# gimbal_controller.net
KiCad netlist of a schematic drawn in EAGLE
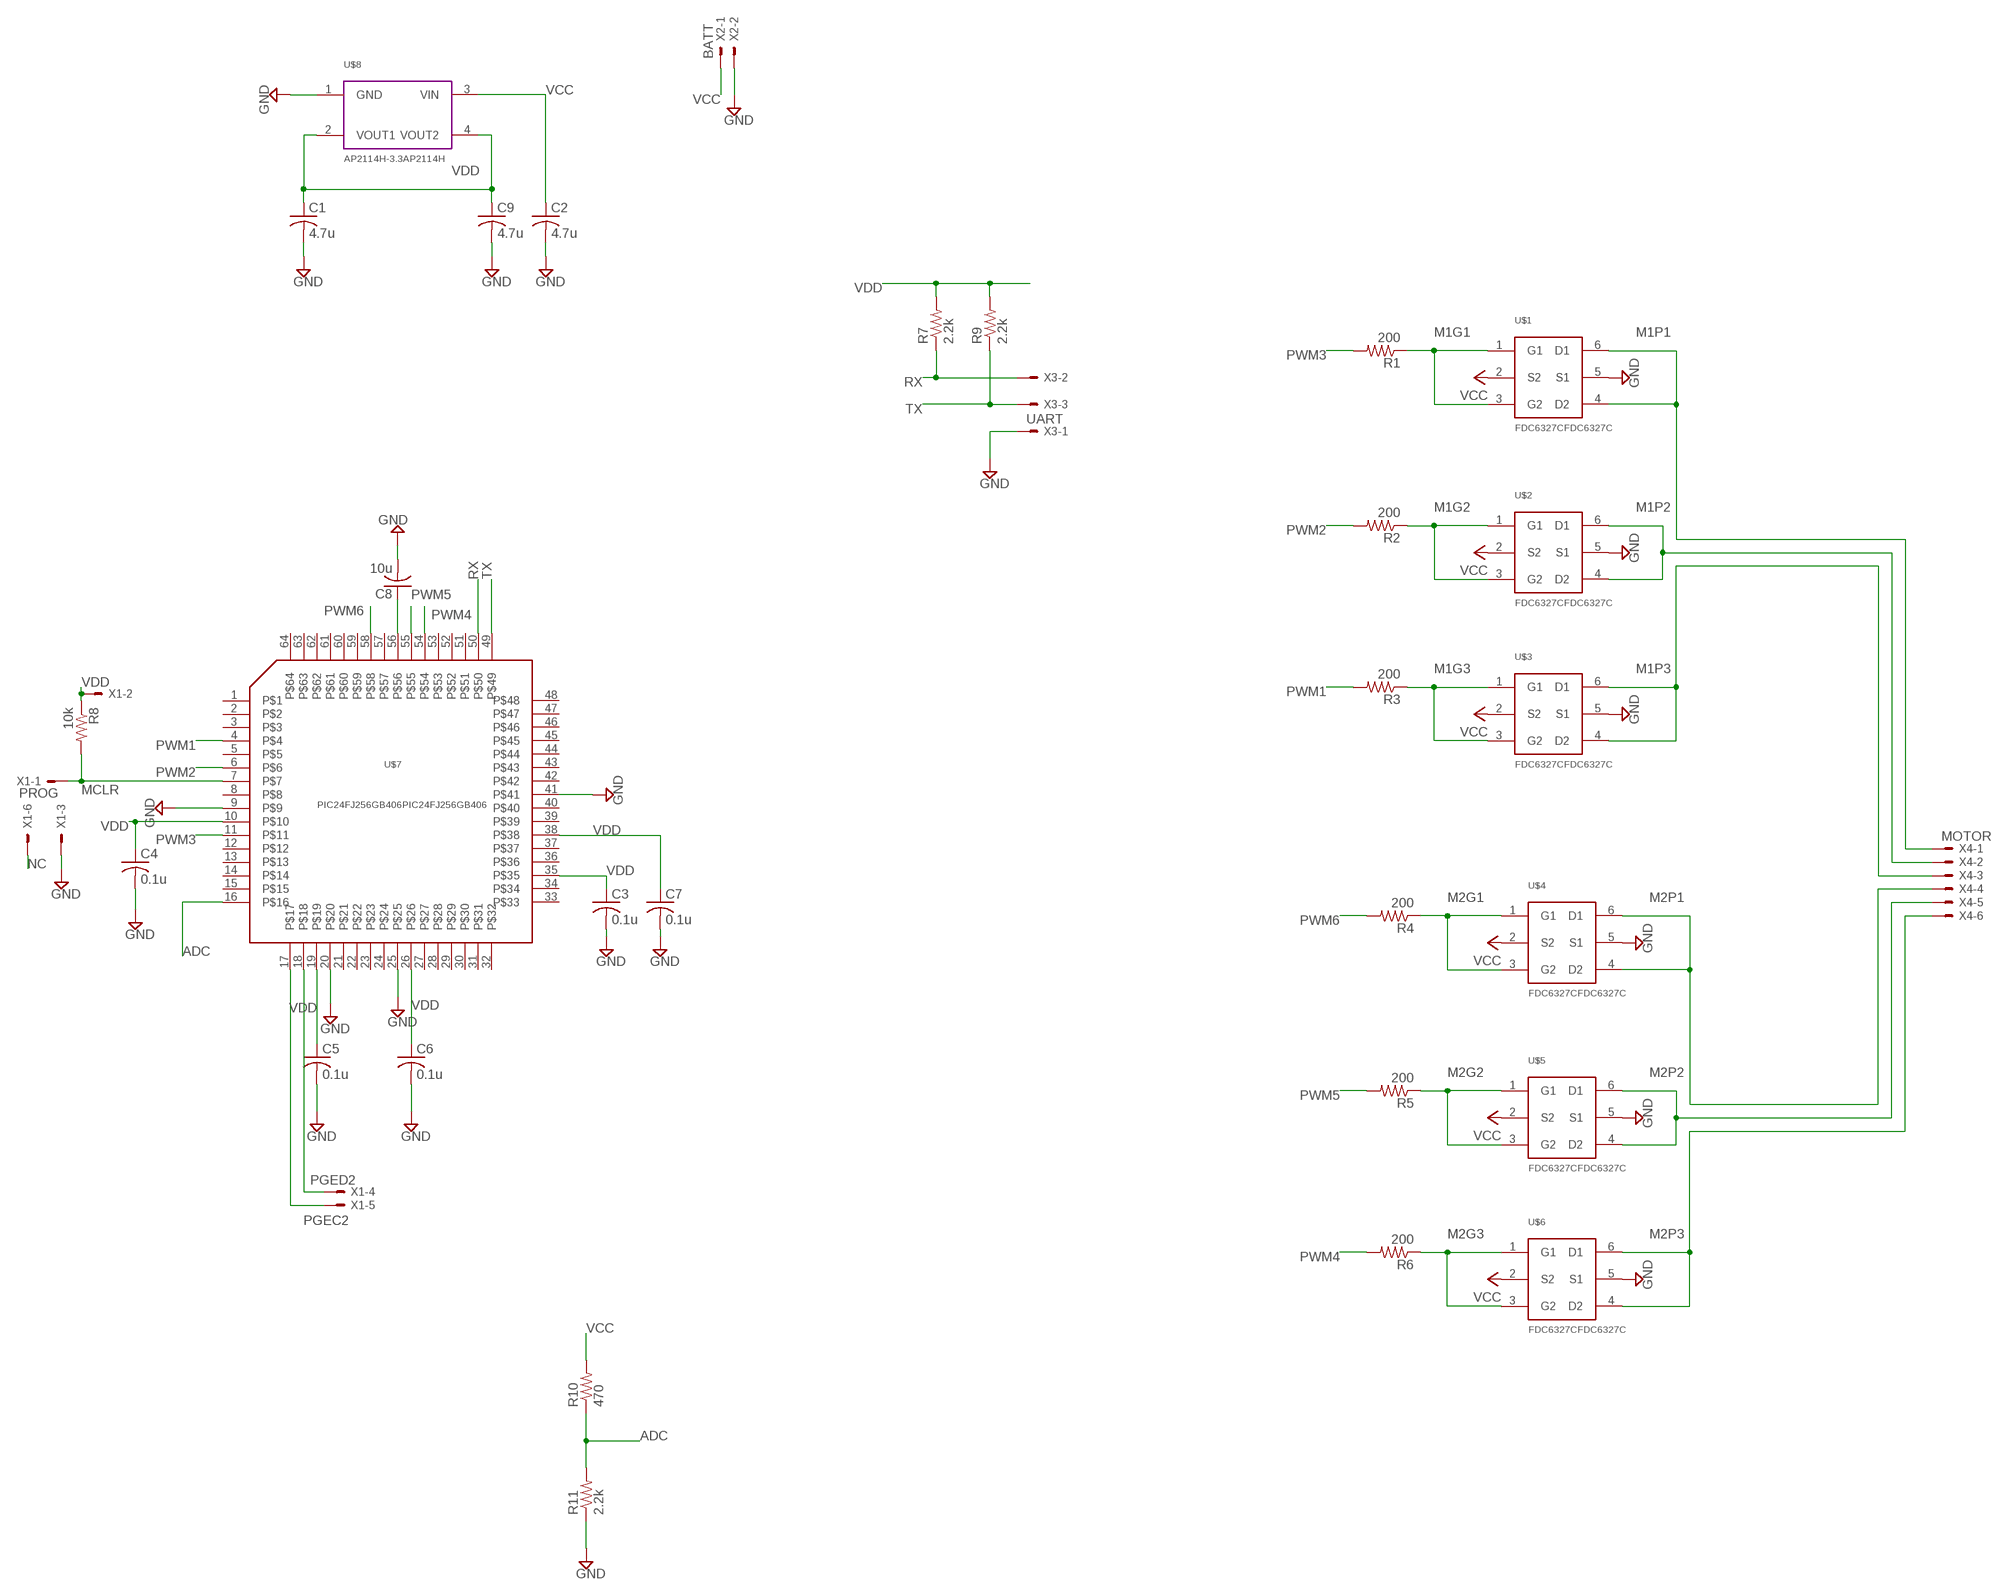
[diagram p0: schematic, sheet 1]

(export (version "E")
  (design (tool "Eeschema 10.0.6"))
  (components
    (comp (ref "C1")
      (value "4.7u")
      (footprint "eagle-import:C0805")
      (libsource (lib "eagle-import") (part "C-USC0805"))
    )
    (comp (ref "C2")
      (value "4.7u")
      (footprint "eagle-import:C0805")
      (libsource (lib "eagle-import") (part "C-USC0805"))
    )
    (comp (ref "C3")
      (value "0.1u")
      (footprint "eagle-import:C0805")
      (libsource (lib "eagle-import") (part "C-USC0805"))
    )
    (comp (ref "C4")
      (value "0.1u")
      (footprint "eagle-import:C0805")
      (libsource (lib "eagle-import") (part "C-USC0805"))
    )
    (comp (ref "C5")
      (value "0.1u")
      (footprint "eagle-import:C0805")
      (libsource (lib "eagle-import") (part "C-USC0805"))
    )
    (comp (ref "C6")
      (value "0.1u")
      (footprint "eagle-import:C0805")
      (libsource (lib "eagle-import") (part "C-USC0805"))
    )
    (comp (ref "C7")
      (value "0.1u")
      (footprint "eagle-import:C0805")
      (libsource (lib "eagle-import") (part "C-USC0805"))
    )
    (comp (ref "C8")
      (value "10u")
      (footprint "eagle-import:C0805")
      (libsource (lib "eagle-import") (part "C-USC0805"))
    )
    (comp (ref "C9")
      (value "4.7u")
      (footprint "eagle-import:C0805")
      (libsource (lib "eagle-import") (part "C-USC0805"))
    )
    (comp (ref "R1")
      (value "200")
      (footprint "eagle-import:R0805")
      (libsource (lib "eagle-import") (part "R-US_R0805"))
    )
    (comp (ref "R2")
      (value "200")
      (footprint "eagle-import:R0805")
      (libsource (lib "eagle-import") (part "R-US_R0805"))
    )
    (comp (ref "R3")
      (value "200")
      (footprint "eagle-import:R0805")
      (libsource (lib "eagle-import") (part "R-US_R0805"))
    )
    (comp (ref "R4")
      (value "200")
      (footprint "eagle-import:R0805")
      (libsource (lib "eagle-import") (part "R-US_R0805"))
    )
    (comp (ref "R5")
      (value "200")
      (footprint "eagle-import:R0805")
      (libsource (lib "eagle-import") (part "R-US_R0805"))
    )
    (comp (ref "R6")
      (value "200")
      (footprint "eagle-import:R0805")
      (libsource (lib "eagle-import") (part "R-US_R0805"))
    )
    (comp (ref "R7")
      (value "2.2k")
      (footprint "eagle-import:R0805")
      (libsource (lib "eagle-import") (part "resistor_R-US_R0805"))
    )
    (comp (ref "R8")
      (value "10k")
      (footprint "eagle-import:R0805")
      (libsource (lib "eagle-import") (part "R-US_R0805"))
    )
    (comp (ref "R9")
      (value "2.2k")
      (footprint "eagle-import:R0805")
      (libsource (lib "eagle-import") (part "resistor_R-US_R0805"))
    )
    (comp (ref "R10")
      (value "470")
      (footprint "eagle-import:R0805")
      (libsource (lib "eagle-import") (part "resistor_R-US_R0805"))
    )
    (comp (ref "R11")
      (value "2.2k")
      (footprint "eagle-import:R0805")
      (libsource (lib "eagle-import") (part "resistor_R-US_R0805"))
    )
    (comp (ref "U$1")
      (value "FDC6327CFDC6327C")
      (footprint "eagle-import:SSOT6")
      (fields (field (name "DIGIKEY_PARTNO") "FDC6327CCT-ND"))
      (libsource (lib "eagle-import") (part "FDC6327CFDC6327C"))
    )
    (comp (ref "U$2")
      (value "FDC6327CFDC6327C")
      (footprint "eagle-import:SSOT6")
      (fields (field (name "DIGIKEY_PARTNO") "FDC6327CCT-ND"))
      (libsource (lib "eagle-import") (part "FDC6327CFDC6327C"))
    )
    (comp (ref "U$3")
      (value "FDC6327CFDC6327C")
      (footprint "eagle-import:SSOT6")
      (fields (field (name "DIGIKEY_PARTNO") "FDC6327CCT-ND"))
      (libsource (lib "eagle-import") (part "FDC6327CFDC6327C"))
    )
    (comp (ref "U$4")
      (value "FDC6327CFDC6327C")
      (footprint "eagle-import:SSOT6")
      (fields (field (name "DIGIKEY_PARTNO") "FDC6327CCT-ND"))
      (libsource (lib "eagle-import") (part "FDC6327CFDC6327C"))
    )
    (comp (ref "U$5")
      (value "FDC6327CFDC6327C")
      (footprint "eagle-import:SSOT6")
      (fields (field (name "DIGIKEY_PARTNO") "FDC6327CCT-ND"))
      (libsource (lib "eagle-import") (part "FDC6327CFDC6327C"))
    )
    (comp (ref "U$6")
      (value "FDC6327CFDC6327C")
      (footprint "eagle-import:SSOT6")
      (fields (field (name "DIGIKEY_PARTNO") "FDC6327CCT-ND"))
      (libsource (lib "eagle-import") (part "FDC6327CFDC6327C"))
    )
    (comp (ref "U$7")
      (value "PIC24FJ256GB406PIC24FJ256GB406")
      (footprint "eagle-import:TQFP64-10X10")
      (fields (field (name "DIGIKEY_PARTNO") "PIC24FJ256GB406-I/PT-ND"))
      (libsource (lib "eagle-import") (part "PIC24FJ256GB406PIC24FJ256GB406"))
    )
    (comp (ref "U$8")
      (value "AP2114H-3.3AP2114H")
      (footprint "eagle-import:SOT223")
      (fields (field (name "DIGIKEY_PARTNO") "AP2114H-3.3TRG1DICT-ND"))
      (libsource (lib "eagle-import") (part "AP2114H-3.3AP2114H"))
    )
    (comp (ref "X1")
      (value "PROG")
      (footprint "eagle-import:22-23-2061")
      (fields (field (name "MF") "MOLEX") (field (name "MPN") "22-23-2061"))
      (libsource (lib "eagle-import") (part "22-23-2061"))
    )
    (comp (ref "X2")
      (value "BATT")
      (footprint "eagle-import:22-23-2021")
      (fields (field (name "MF") "MOLEX") (field (name "MPN") "22-23-2021"))
      (libsource (lib "eagle-import") (part "22-23-2021"))
    )
    (comp (ref "X3")
      (value "UART")
      (footprint "eagle-import:22-23-2031")
      (fields (field (name "MF") "MOLEX") (field (name "MPN") "22-23-2031"))
      (libsource (lib "eagle-import") (part "22-23-2031"))
    )
    (comp (ref "X4")
      (value "MOTOR")
      (footprint "eagle-import:22-23-2061")
      (fields (field (name "MF") "MOLEX") (field (name "MPN") "22-23-2061"))
      (libsource (lib "eagle-import") (part "22-23-2061"))
    )
  )
  (nets
    (net (code "1") (name "/ADC") (class "Default")
      (node (ref "R10") (pin "1") (pinfunction "1_1") (pintype "passive"))
      (node (ref "R11") (pin "2") (pinfunction "2_2") (pintype "passive"))
      (node (ref "U$7") (pin "16") (pinfunction "P$16_16") (pintype "bidirectional"))
    )
    (net (code "2") (name "/M1G1") (class "Default")
      (node (ref "R1") (pin "1") (pinfunction "1_1") (pintype "passive"))
      (node (ref "U$1") (pin "1") (pinfunction "G1_1") (pintype "bidirectional"))
      (node (ref "U$1") (pin "3") (pinfunction "G2_3") (pintype "bidirectional"))
    )
    (net (code "3") (name "/M1G2") (class "Default")
      (node (ref "R2") (pin "1") (pinfunction "1_1") (pintype "passive"))
      (node (ref "U$2") (pin "1") (pinfunction "G1_1") (pintype "bidirectional"))
      (node (ref "U$2") (pin "3") (pinfunction "G2_3") (pintype "bidirectional"))
    )
    (net (code "4") (name "/M1G3") (class "Default")
      (node (ref "R3") (pin "1") (pinfunction "1_1") (pintype "passive"))
      (node (ref "U$3") (pin "1") (pinfunction "G1_1") (pintype "bidirectional"))
      (node (ref "U$3") (pin "3") (pinfunction "G2_3") (pintype "bidirectional"))
    )
    (net (code "5") (name "/M1P1") (class "Default")
      (node (ref "U$1") (pin "4") (pinfunction "D2_4") (pintype "bidirectional"))
      (node (ref "U$1") (pin "6") (pinfunction "D1_6") (pintype "bidirectional"))
      (node (ref "X4") (pin "1") (pinfunction "S_1") (pintype "passive"))
    )
    (net (code "6") (name "/M1P2") (class "Default")
      (node (ref "U$2") (pin "4") (pinfunction "D2_4") (pintype "bidirectional"))
      (node (ref "U$2") (pin "6") (pinfunction "D1_6") (pintype "bidirectional"))
      (node (ref "X4") (pin "2") (pinfunction "S_2") (pintype "passive"))
    )
    (net (code "7") (name "/M1P3") (class "Default")
      (node (ref "U$3") (pin "4") (pinfunction "D2_4") (pintype "bidirectional"))
      (node (ref "U$3") (pin "6") (pinfunction "D1_6") (pintype "bidirectional"))
      (node (ref "X4") (pin "3") (pinfunction "S_3") (pintype "passive"))
    )
    (net (code "8") (name "/M2G1") (class "Default")
      (node (ref "R4") (pin "1") (pinfunction "1_1") (pintype "passive"))
      (node (ref "U$4") (pin "1") (pinfunction "G1_1") (pintype "bidirectional"))
      (node (ref "U$4") (pin "3") (pinfunction "G2_3") (pintype "bidirectional"))
    )
    (net (code "9") (name "/M2G2") (class "Default")
      (node (ref "R5") (pin "1") (pinfunction "1_1") (pintype "passive"))
      (node (ref "U$5") (pin "1") (pinfunction "G1_1") (pintype "bidirectional"))
      (node (ref "U$5") (pin "3") (pinfunction "G2_3") (pintype "bidirectional"))
    )
    (net (code "10") (name "/M2G3") (class "Default")
      (node (ref "R6") (pin "1") (pinfunction "1_1") (pintype "passive"))
      (node (ref "U$6") (pin "1") (pinfunction "G1_1") (pintype "bidirectional"))
      (node (ref "U$6") (pin "3") (pinfunction "G2_3") (pintype "bidirectional"))
    )
    (net (code "11") (name "/M2P1") (class "Default")
      (node (ref "U$4") (pin "4") (pinfunction "D2_4") (pintype "bidirectional"))
      (node (ref "U$4") (pin "6") (pinfunction "D1_6") (pintype "bidirectional"))
      (node (ref "X4") (pin "4") (pinfunction "S_4") (pintype "passive"))
    )
    (net (code "12") (name "/M2P2") (class "Default")
      (node (ref "U$5") (pin "4") (pinfunction "D2_4") (pintype "bidirectional"))
      (node (ref "U$5") (pin "6") (pinfunction "D1_6") (pintype "bidirectional"))
      (node (ref "X4") (pin "5") (pinfunction "S_5") (pintype "passive"))
    )
    (net (code "13") (name "/M2P3") (class "Default")
      (node (ref "U$6") (pin "4") (pinfunction "D2_4") (pintype "bidirectional"))
      (node (ref "U$6") (pin "6") (pinfunction "D1_6") (pintype "bidirectional"))
      (node (ref "X4") (pin "6") (pinfunction "S_6") (pintype "passive"))
    )
    (net (code "14") (name "/MCLR") (class "Default")
      (node (ref "R8") (pin "2") (pinfunction "2_2") (pintype "passive"))
      (node (ref "U$7") (pin "7") (pinfunction "P$7_7") (pintype "bidirectional"))
      (node (ref "X1") (pin "1") (pinfunction "S_1") (pintype "passive"))
    )
    (net (code "15") (name "/NC") (class "Default")
      (node (ref "X1") (pin "6") (pinfunction "S_6") (pintype "passive"))
    )
    (net (code "16") (name "/PGEC2") (class "Default")
      (node (ref "U$7") (pin "17") (pinfunction "P$17_17") (pintype "bidirectional"))
      (node (ref "X1") (pin "5") (pinfunction "S_5") (pintype "passive"))
    )
    (net (code "17") (name "/PGED2") (class "Default")
      (node (ref "U$7") (pin "18") (pinfunction "P$18_18") (pintype "bidirectional"))
      (node (ref "X1") (pin "4") (pinfunction "S_4") (pintype "passive"))
    )
    (net (code "18") (name "/PWM1") (class "Default")
      (node (ref "R3") (pin "2") (pinfunction "2_2") (pintype "passive"))
      (node (ref "U$7") (pin "4") (pinfunction "P$4_4") (pintype "bidirectional"))
    )
    (net (code "19") (name "/PWM2") (class "Default")
      (node (ref "R2") (pin "2") (pinfunction "2_2") (pintype "passive"))
      (node (ref "U$7") (pin "6") (pinfunction "P$6_6") (pintype "bidirectional"))
    )
    (net (code "20") (name "/PWM3") (class "Default")
      (node (ref "R1") (pin "2") (pinfunction "2_2") (pintype "passive"))
      (node (ref "U$7") (pin "11") (pinfunction "P$11_11") (pintype "bidirectional"))
    )
    (net (code "21") (name "/PWM4") (class "Default")
      (node (ref "R6") (pin "2") (pinfunction "2_2") (pintype "passive"))
      (node (ref "U$7") (pin "54") (pinfunction "P$54_54") (pintype "bidirectional"))
    )
    (net (code "22") (name "/PWM5") (class "Default")
      (node (ref "R5") (pin "2") (pinfunction "2_2") (pintype "passive"))
      (node (ref "U$7") (pin "55") (pinfunction "P$55_55") (pintype "bidirectional"))
    )
    (net (code "23") (name "/PWM6") (class "Default")
      (node (ref "R4") (pin "2") (pinfunction "2_2") (pintype "passive"))
      (node (ref "U$7") (pin "58") (pinfunction "P$58_58") (pintype "bidirectional"))
    )
    (net (code "24") (name "/RX") (class "Default")
      (node (ref "R7") (pin "1") (pinfunction "1_1") (pintype "passive"))
      (node (ref "U$7") (pin "50") (pinfunction "P$50_50") (pintype "bidirectional"))
      (node (ref "X3") (pin "2") (pinfunction "S_2") (pintype "passive"))
    )
    (net (code "25") (name "/TX") (class "Default")
      (node (ref "R9") (pin "1") (pinfunction "1_1") (pintype "passive"))
      (node (ref "U$7") (pin "49") (pinfunction "P$49_49") (pintype "bidirectional"))
      (node (ref "X3") (pin "3") (pinfunction "S_3") (pintype "passive"))
    )
    (net (code "26") (name "/VDD") (class "Default")
      (node (ref "C1") (pin "1") (pinfunction "1_1") (pintype "passive"))
      (node (ref "C3") (pin "1") (pinfunction "1_1") (pintype "passive"))
      (node (ref "C4") (pin "1") (pinfunction "1_1") (pintype "passive"))
      (node (ref "C5") (pin "1") (pinfunction "1_1") (pintype "passive"))
      (node (ref "C6") (pin "1") (pinfunction "1_1") (pintype "passive"))
      (node (ref "C7") (pin "1") (pinfunction "1_1") (pintype "passive"))
      (node (ref "C9") (pin "1") (pinfunction "1_1") (pintype "passive"))
      (node (ref "R7") (pin "2") (pinfunction "2_2") (pintype "passive"))
      (node (ref "R8") (pin "1") (pinfunction "1_1") (pintype "passive"))
      (node (ref "R9") (pin "2") (pinfunction "2_2") (pintype "passive"))
      (node (ref "U$7") (pin "10") (pinfunction "P$10_10") (pintype "bidirectional"))
      (node (ref "U$7") (pin "19") (pinfunction "P$19_19") (pintype "bidirectional"))
      (node (ref "U$7") (pin "26") (pinfunction "P$26_26") (pintype "bidirectional"))
      (node (ref "U$7") (pin "35") (pinfunction "P$35_35") (pintype "bidirectional"))
      (node (ref "U$7") (pin "38") (pinfunction "P$38_38") (pintype "bidirectional"))
      (node (ref "U$8") (pin "2") (pinfunction "VOUT1_2") (pintype "bidirectional"))
      (node (ref "U$8") (pin "4") (pinfunction "VOUT2_4") (pintype "bidirectional"))
      (node (ref "X1") (pin "2") (pinfunction "S_2") (pintype "passive"))
    )
    (net (code "27") (name "GND") (class "Default")
      (node (ref "C1") (pin "2") (pinfunction "2_2") (pintype "passive"))
      (node (ref "C2") (pin "2") (pinfunction "2_2") (pintype "passive"))
      (node (ref "C3") (pin "2") (pinfunction "2_2") (pintype "passive"))
      (node (ref "C4") (pin "2") (pinfunction "2_2") (pintype "passive"))
      (node (ref "C5") (pin "2") (pinfunction "2_2") (pintype "passive"))
      (node (ref "C6") (pin "2") (pinfunction "2_2") (pintype "passive"))
      (node (ref "C7") (pin "2") (pinfunction "2_2") (pintype "passive"))
      (node (ref "C8") (pin "2") (pinfunction "2_2") (pintype "passive"))
      (node (ref "C9") (pin "2") (pinfunction "2_2") (pintype "passive"))
      (node (ref "R11") (pin "1") (pinfunction "1_1") (pintype "passive"))
      (node (ref "U$1") (pin "5") (pinfunction "S1_5") (pintype "bidirectional"))
      (node (ref "U$2") (pin "5") (pinfunction "S1_5") (pintype "bidirectional"))
      (node (ref "U$3") (pin "5") (pinfunction "S1_5") (pintype "bidirectional"))
      (node (ref "U$4") (pin "5") (pinfunction "S1_5") (pintype "bidirectional"))
      (node (ref "U$5") (pin "5") (pinfunction "S1_5") (pintype "bidirectional"))
      (node (ref "U$6") (pin "5") (pinfunction "S1_5") (pintype "bidirectional"))
      (node (ref "U$7") (pin "20") (pinfunction "P$20_20") (pintype "bidirectional"))
      (node (ref "U$7") (pin "25") (pinfunction "P$25_25") (pintype "bidirectional"))
      (node (ref "U$7") (pin "41") (pinfunction "P$41_41") (pintype "bidirectional"))
      (node (ref "U$7") (pin "9") (pinfunction "P$9_9") (pintype "bidirectional"))
      (node (ref "U$8") (pin "1") (pinfunction "GND_1") (pintype "bidirectional"))
      (node (ref "X1") (pin "3") (pinfunction "S_3") (pintype "passive"))
      (node (ref "X2") (pin "2") (pinfunction "S_2") (pintype "passive"))
      (node (ref "X3") (pin "1") (pinfunction "S_1") (pintype "passive"))
    )
    (net (code "28") (name "Net-(U$7-P$56)") (class "Default")
      (node (ref "C8") (pin "1") (pinfunction "1_1") (pintype "passive"))
      (node (ref "U$7") (pin "56") (pinfunction "P$56_56") (pintype "bidirectional"))
    )
    (net (code "29") (name "VCC") (class "Default")
      (node (ref "C2") (pin "1") (pinfunction "1_1") (pintype "passive"))
      (node (ref "R10") (pin "2") (pinfunction "2_2") (pintype "passive"))
      (node (ref "U$1") (pin "2") (pinfunction "S2_2") (pintype "bidirectional"))
      (node (ref "U$2") (pin "2") (pinfunction "S2_2") (pintype "bidirectional"))
      (node (ref "U$3") (pin "2") (pinfunction "S2_2") (pintype "bidirectional"))
      (node (ref "U$4") (pin "2") (pinfunction "S2_2") (pintype "bidirectional"))
      (node (ref "U$5") (pin "2") (pinfunction "S2_2") (pintype "bidirectional"))
      (node (ref "U$6") (pin "2") (pinfunction "S2_2") (pintype "bidirectional"))
      (node (ref "U$8") (pin "3") (pinfunction "VIN_3") (pintype "bidirectional"))
      (node (ref "X2") (pin "1") (pinfunction "S_1") (pintype "passive"))
    )
    (net (code "30") (name "unconnected-(U$7-P$1-Pad1)") (class "Default")
      (node (ref "U$7") (pin "1") (pinfunction "P$1_1") (pintype "bidirectional"))
    )
    (net (code "31") (name "unconnected-(U$7-P$2-Pad2)") (class "Default")
      (node (ref "U$7") (pin "2") (pinfunction "P$2_2") (pintype "bidirectional"))
    )
    (net (code "32") (name "unconnected-(U$7-P$3-Pad3)") (class "Default")
      (node (ref "U$7") (pin "3") (pinfunction "P$3_3") (pintype "bidirectional"))
    )
    (net (code "33") (name "unconnected-(U$7-P$5-Pad5)") (class "Default")
      (node (ref "U$7") (pin "5") (pinfunction "P$5_5") (pintype "bidirectional"))
    )
    (net (code "34") (name "unconnected-(U$7-P$8-Pad8)") (class "Default")
      (node (ref "U$7") (pin "8") (pinfunction "P$8_8") (pintype "bidirectional"))
    )
    (net (code "35") (name "unconnected-(U$7-P$12-Pad12)") (class "Default")
      (node (ref "U$7") (pin "12") (pinfunction "P$12_12") (pintype "bidirectional"))
    )
    (net (code "36") (name "unconnected-(U$7-P$13-Pad13)") (class "Default")
      (node (ref "U$7") (pin "13") (pinfunction "P$13_13") (pintype "bidirectional"))
    )
    (net (code "37") (name "unconnected-(U$7-P$14-Pad14)") (class "Default")
      (node (ref "U$7") (pin "14") (pinfunction "P$14_14") (pintype "bidirectional"))
    )
    (net (code "38") (name "unconnected-(U$7-P$15-Pad15)") (class "Default")
      (node (ref "U$7") (pin "15") (pinfunction "P$15_15") (pintype "bidirectional"))
    )
    (net (code "39") (name "unconnected-(U$7-P$21-Pad21)") (class "Default")
      (node (ref "U$7") (pin "21") (pinfunction "P$21_21") (pintype "bidirectional"))
    )
    (net (code "40") (name "unconnected-(U$7-P$22-Pad22)") (class "Default")
      (node (ref "U$7") (pin "22") (pinfunction "P$22_22") (pintype "bidirectional"))
    )
    (net (code "41") (name "unconnected-(U$7-P$23-Pad23)") (class "Default")
      (node (ref "U$7") (pin "23") (pinfunction "P$23_23") (pintype "bidirectional"))
    )
    (net (code "42") (name "unconnected-(U$7-P$24-Pad24)") (class "Default")
      (node (ref "U$7") (pin "24") (pinfunction "P$24_24") (pintype "bidirectional"))
    )
    (net (code "43") (name "unconnected-(U$7-P$27-Pad27)") (class "Default")
      (node (ref "U$7") (pin "27") (pinfunction "P$27_27") (pintype "bidirectional"))
    )
    (net (code "44") (name "unconnected-(U$7-P$28-Pad28)") (class "Default")
      (node (ref "U$7") (pin "28") (pinfunction "P$28_28") (pintype "bidirectional"))
    )
    (net (code "45") (name "unconnected-(U$7-P$29-Pad29)") (class "Default")
      (node (ref "U$7") (pin "29") (pinfunction "P$29_29") (pintype "bidirectional"))
    )
    (net (code "46") (name "unconnected-(U$7-P$30-Pad30)") (class "Default")
      (node (ref "U$7") (pin "30") (pinfunction "P$30_30") (pintype "bidirectional"))
    )
    (net (code "47") (name "unconnected-(U$7-P$31-Pad31)") (class "Default")
      (node (ref "U$7") (pin "31") (pinfunction "P$31_31") (pintype "bidirectional"))
    )
    (net (code "48") (name "unconnected-(U$7-P$32-Pad32)") (class "Default")
      (node (ref "U$7") (pin "32") (pinfunction "P$32_32") (pintype "bidirectional"))
    )
    (net (code "49") (name "unconnected-(U$7-P$33-Pad33)") (class "Default")
      (node (ref "U$7") (pin "33") (pinfunction "P$33_33") (pintype "bidirectional"))
    )
    (net (code "50") (name "unconnected-(U$7-P$34-Pad34)") (class "Default")
      (node (ref "U$7") (pin "34") (pinfunction "P$34_34") (pintype "bidirectional"))
    )
    (net (code "51") (name "unconnected-(U$7-P$36-Pad36)") (class "Default")
      (node (ref "U$7") (pin "36") (pinfunction "P$36_36") (pintype "bidirectional"))
    )
    (net (code "52") (name "unconnected-(U$7-P$37-Pad37)") (class "Default")
      (node (ref "U$7") (pin "37") (pinfunction "P$37_37") (pintype "bidirectional"))
    )
    (net (code "53") (name "unconnected-(U$7-P$39-Pad39)") (class "Default")
      (node (ref "U$7") (pin "39") (pinfunction "P$39_39") (pintype "bidirectional"))
    )
    (net (code "54") (name "unconnected-(U$7-P$40-Pad40)") (class "Default")
      (node (ref "U$7") (pin "40") (pinfunction "P$40_40") (pintype "bidirectional"))
    )
    (net (code "55") (name "unconnected-(U$7-P$42-Pad42)") (class "Default")
      (node (ref "U$7") (pin "42") (pinfunction "P$42_42") (pintype "bidirectional"))
    )
    (net (code "56") (name "unconnected-(U$7-P$43-Pad43)") (class "Default")
      (node (ref "U$7") (pin "43") (pinfunction "P$43_43") (pintype "bidirectional"))
    )
    (net (code "57") (name "unconnected-(U$7-P$44-Pad44)") (class "Default")
      (node (ref "U$7") (pin "44") (pinfunction "P$44_44") (pintype "bidirectional"))
    )
    (net (code "58") (name "unconnected-(U$7-P$45-Pad45)") (class "Default")
      (node (ref "U$7") (pin "45") (pinfunction "P$45_45") (pintype "bidirectional"))
    )
    (net (code "59") (name "unconnected-(U$7-P$46-Pad46)") (class "Default")
      (node (ref "U$7") (pin "46") (pinfunction "P$46_46") (pintype "bidirectional"))
    )
    (net (code "60") (name "unconnected-(U$7-P$47-Pad47)") (class "Default")
      (node (ref "U$7") (pin "47") (pinfunction "P$47_47") (pintype "bidirectional"))
    )
    (net (code "61") (name "unconnected-(U$7-P$48-Pad48)") (class "Default")
      (node (ref "U$7") (pin "48") (pinfunction "P$48_48") (pintype "bidirectional"))
    )
    (net (code "62") (name "unconnected-(U$7-P$51-Pad51)") (class "Default")
      (node (ref "U$7") (pin "51") (pinfunction "P$51_51") (pintype "bidirectional"))
    )
    (net (code "63") (name "unconnected-(U$7-P$52-Pad52)") (class "Default")
      (node (ref "U$7") (pin "52") (pinfunction "P$52_52") (pintype "bidirectional"))
    )
    (net (code "64") (name "unconnected-(U$7-P$53-Pad53)") (class "Default")
      (node (ref "U$7") (pin "53") (pinfunction "P$53_53") (pintype "bidirectional"))
    )
    (net (code "65") (name "unconnected-(U$7-P$57-Pad57)") (class "Default")
      (node (ref "U$7") (pin "57") (pinfunction "P$57_57") (pintype "bidirectional"))
    )
    (net (code "66") (name "unconnected-(U$7-P$59-Pad59)") (class "Default")
      (node (ref "U$7") (pin "59") (pinfunction "P$59_59") (pintype "bidirectional"))
    )
    (net (code "67") (name "unconnected-(U$7-P$60-Pad60)") (class "Default")
      (node (ref "U$7") (pin "60") (pinfunction "P$60_60") (pintype "bidirectional"))
    )
    (net (code "68") (name "unconnected-(U$7-P$61-Pad61)") (class "Default")
      (node (ref "U$7") (pin "61") (pinfunction "P$61_61") (pintype "bidirectional"))
    )
    (net (code "69") (name "unconnected-(U$7-P$62-Pad62)") (class "Default")
      (node (ref "U$7") (pin "62") (pinfunction "P$62_62") (pintype "bidirectional"))
    )
    (net (code "70") (name "unconnected-(U$7-P$63-Pad63)") (class "Default")
      (node (ref "U$7") (pin "63") (pinfunction "P$63_63") (pintype "bidirectional"))
    )
    (net (code "71") (name "unconnected-(U$7-P$64-Pad64)") (class "Default")
      (node (ref "U$7") (pin "64") (pinfunction "P$64_64") (pintype "bidirectional"))
    )
  )
)
